# lampe.net
KiCad netlist of a schematic drawn in EAGLE
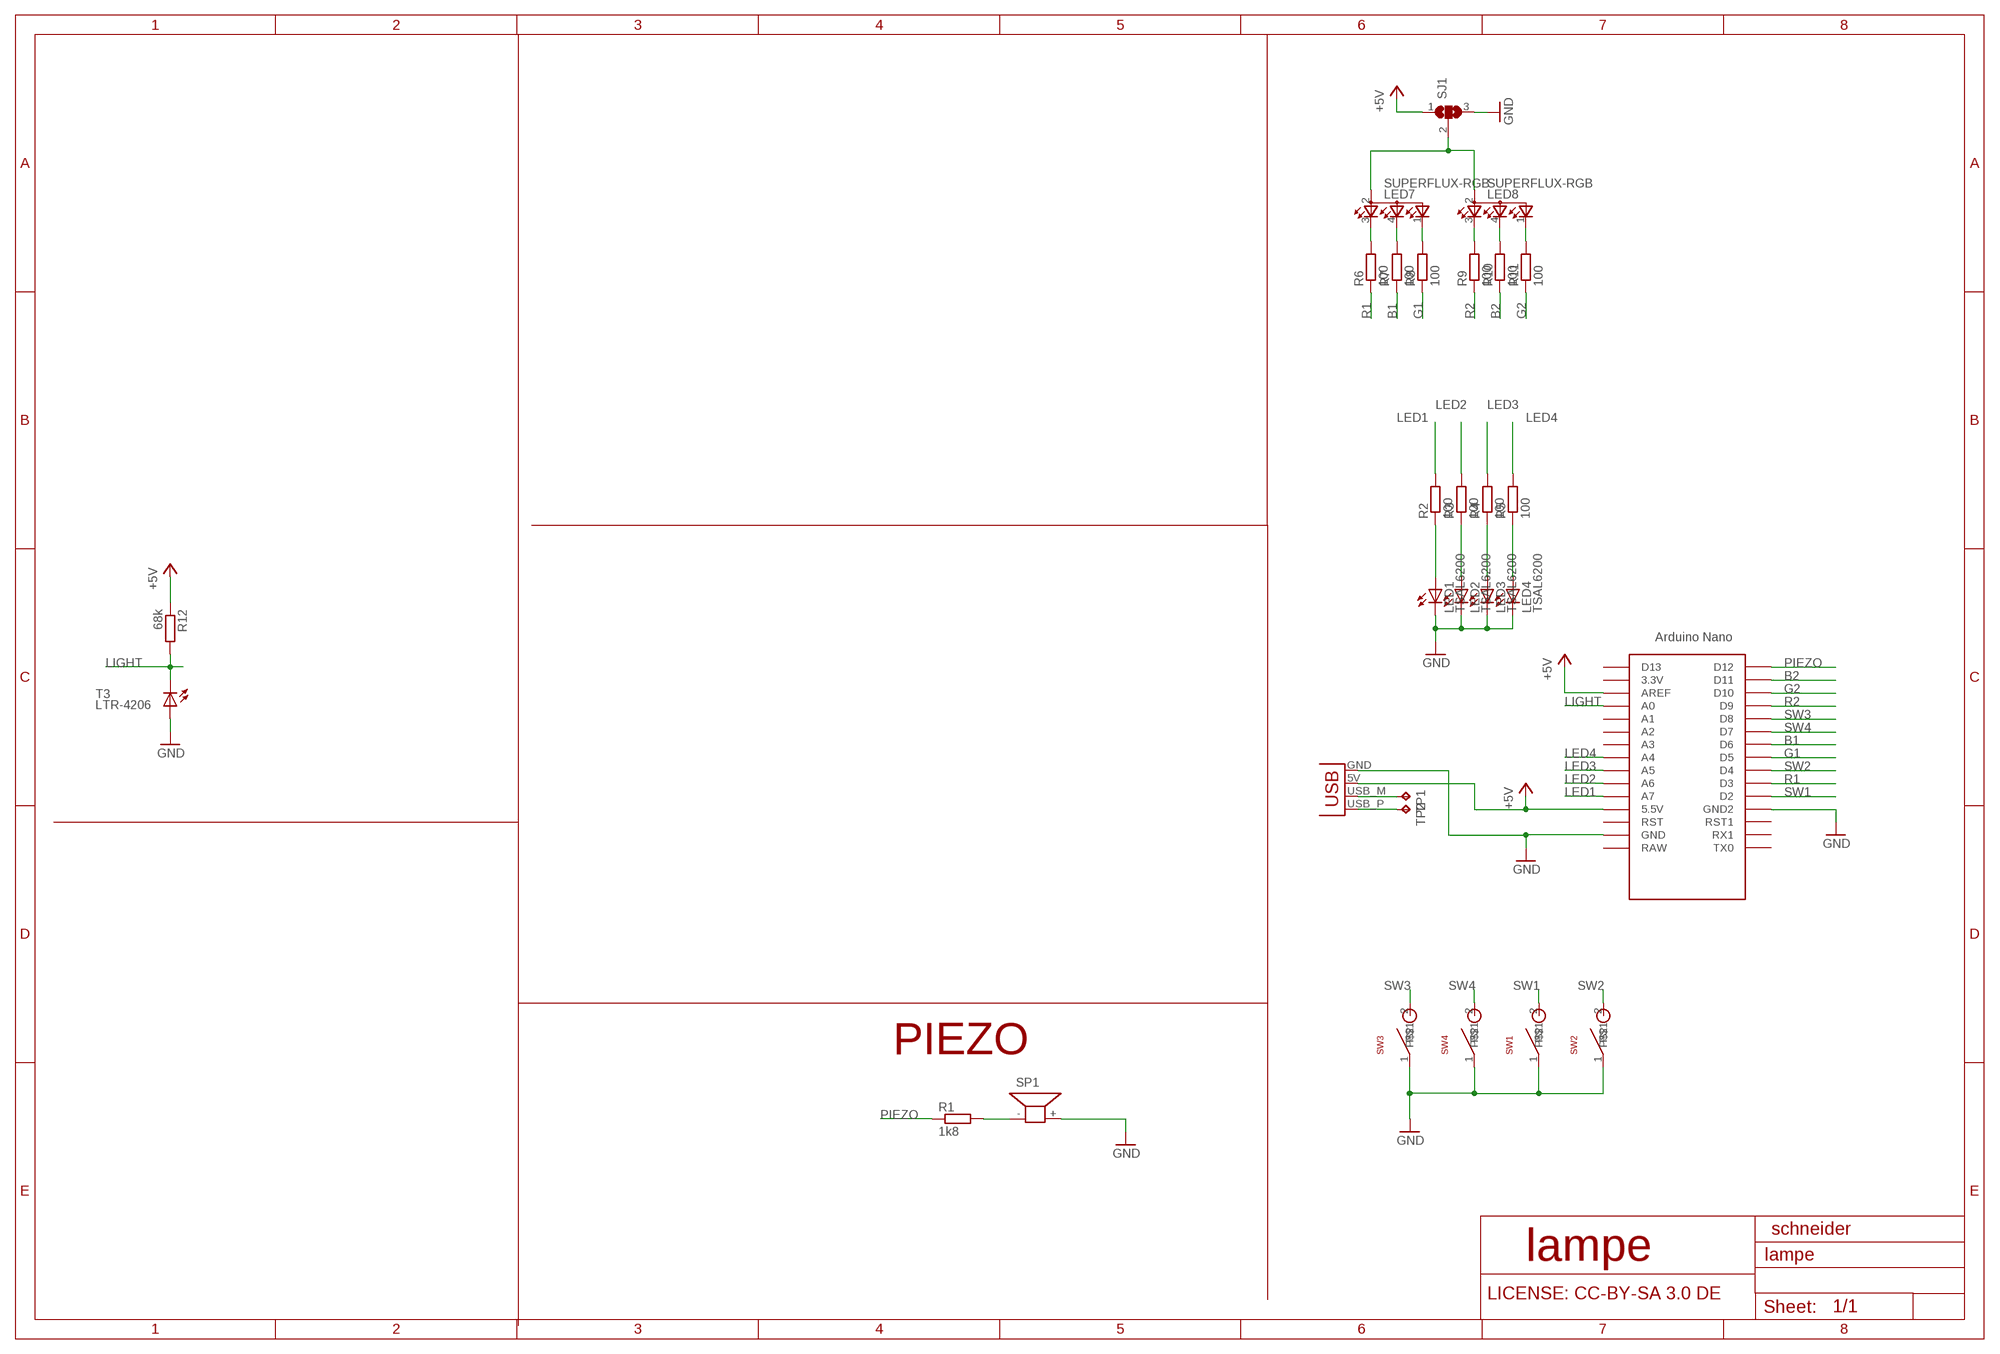
[diagram p0: schematic, sheet 1]

(export (version "E")
  (design (tool "Eeschema 10.0.6"))
  (components
    (comp (ref "LED1")
      (value "TSAL6200")
      (footprint "eagle-import:LED5MM")
      (libsource (lib "eagle-import") (part "LED5MM"))
    )
    (comp (ref "LED2")
      (value "TSAL6200")
      (footprint "eagle-import:LED5MM")
      (libsource (lib "eagle-import") (part "LED5MM"))
    )
    (comp (ref "LED3")
      (value "TSAL6200")
      (footprint "eagle-import:LED5MM")
      (libsource (lib "eagle-import") (part "LED5MM"))
    )
    (comp (ref "LED4")
      (value "TSAL6200")
      (footprint "eagle-import:LED5MM")
      (libsource (lib "eagle-import") (part "LED5MM"))
    )
    (comp (ref "LED7")
      (value "SUPERFLUX-RGB")
      (footprint "eagle-import:SUPERFLUX-7.6X7.6")
      (libsource (lib "eagle-import") (part "SUPERFLUX-RGB"))
    )
    (comp (ref "LED8")
      (value "SUPERFLUX-RGB")
      (footprint "eagle-import:SUPERFLUX-7.6X7.6")
      (libsource (lib "eagle-import") (part "SUPERFLUX-RGB"))
    )
    (comp (ref "R1")
      (value "1k8")
      (footprint "eagle-import:0207_7")
      (libsource (lib "eagle-import") (part "R-EU_0207/7"))
    )
    (comp (ref "R2")
      (value "100")
      (footprint "eagle-import:0207_7")
      (libsource (lib "eagle-import") (part "R-EU_0207/7"))
    )
    (comp (ref "R3")
      (value "100")
      (footprint "eagle-import:0207_7")
      (libsource (lib "eagle-import") (part "R-EU_0207/7"))
    )
    (comp (ref "R4")
      (value "100")
      (footprint "eagle-import:0207_7")
      (libsource (lib "eagle-import") (part "R-EU_0207/7"))
    )
    (comp (ref "R5")
      (value "100")
      (footprint "eagle-import:0207_7")
      (libsource (lib "eagle-import") (part "R-EU_0207/7"))
    )
    (comp (ref "R6")
      (value "100")
      (footprint "eagle-import:0207_7")
      (libsource (lib "eagle-import") (part "R-EU_0207/7"))
    )
    (comp (ref "R7")
      (value "100")
      (footprint "eagle-import:0207_7")
      (libsource (lib "eagle-import") (part "R-EU_0207/7"))
    )
    (comp (ref "R8")
      (value "100")
      (footprint "eagle-import:0207_7")
      (libsource (lib "eagle-import") (part "R-EU_0207/7"))
    )
    (comp (ref "R9")
      (value "100")
      (footprint "eagle-import:0207_7")
      (libsource (lib "eagle-import") (part "R-EU_0207/7"))
    )
    (comp (ref "R10")
      (value "100")
      (footprint "eagle-import:0207_7")
      (libsource (lib "eagle-import") (part "R-EU_0207/7"))
    )
    (comp (ref "R11")
      (value "100")
      (footprint "eagle-import:0207_7")
      (libsource (lib "eagle-import") (part "R-EU_0207/7"))
    )
    (comp (ref "R12")
      (value "68k")
      (footprint "eagle-import:0207_7")
      (libsource (lib "eagle-import") (part "R-EU_0207/7"))
    )
    (comp (ref "SJ1")
      (value "SJ2W")
      (footprint "eagle-import:SJ_2")
      (libsource (lib "eagle-import") (part "SJ2W"))
    )
    (comp (ref "SP1")
      (value "AL11P")
      (footprint "eagle-import:AL11P")
      (libsource (lib "eagle-import") (part "AL11P"))
    )
    (comp (ref "SW1")
      (value "SWITCH")
      (footprint "eagle-import:SWITCH")
      (libsource (lib "eagle-import") (part "SWITCH"))
    )
    (comp (ref "SW2")
      (value "SWITCH")
      (footprint "eagle-import:SWITCH")
      (libsource (lib "eagle-import") (part "SWITCH"))
    )
    (comp (ref "SW3")
      (value "SWITCH")
      (footprint "eagle-import:SWITCH")
      (libsource (lib "eagle-import") (part "SWITCH"))
    )
    (comp (ref "SW4")
      (value "SWITCH")
      (footprint "eagle-import:SWITCH")
      (libsource (lib "eagle-import") (part "SWITCH"))
    )
    (comp (ref "T3")
      (value "LTR-4206")
      (footprint "eagle-import:LED3MM")
      (libsource (lib "eagle-import") (part "LED3MM"))
    )
    (comp (ref "TP1")
      (value "TPB1,27")
      (footprint "eagle-import:B1,27")
      (libsource (lib "eagle-import") (part "TPB1,27"))
    )
    (comp (ref "TP2")
      (value "TPB1,27")
      (footprint "eagle-import:B1,27")
      (libsource (lib "eagle-import") (part "TPB1,27"))
    )
    (comp (ref "U$1")
      (value "NANO")
      (footprint "eagle-import:NANO")
      (libsource (lib "eagle-import") (part "NANO"))
    )
    (comp (ref "X1")
      (value "USBPCB")
      (footprint "eagle-import:USB-A-PCB")
      (libsource (lib "eagle-import") (part "USBPCB"))
    )
  )
  (nets
    (net (code "1") (name "+5V") (class "Default")
      (node (ref "R12") (pin "1") (pinfunction "1_1") (pintype "passive"))
      (node (ref "SJ1") (pin "1") (pinfunction "1_1") (pintype "passive"))
      (node (ref "U$1") (pin "5V") (pinfunction "5.5V_5V") (pintype "bidirectional"))
      (node (ref "U$1") (pin "AREF") (pinfunction "AREF_AREF") (pintype "bidirectional"))
      (node (ref "X1") (pin "5V") (pinfunction "VBUS_5V") (pintype "bidirectional"))
    )
    (net (code "2") (name "/B1") (class "Default")
      (node (ref "R7") (pin "1") (pinfunction "1_1") (pintype "passive"))
      (node (ref "U$1") (pin "D6") (pinfunction "D6_D6") (pintype "bidirectional"))
    )
    (net (code "3") (name "/B2") (class "Default")
      (node (ref "R10") (pin "1") (pinfunction "1_1") (pintype "passive"))
      (node (ref "U$1") (pin "D11") (pinfunction "D11_D11") (pintype "bidirectional"))
    )
    (net (code "4") (name "/G1") (class "Default")
      (node (ref "R8") (pin "1") (pinfunction "1_1") (pintype "passive"))
      (node (ref "U$1") (pin "D5") (pinfunction "D5_D5") (pintype "bidirectional"))
    )
    (net (code "5") (name "/G2") (class "Default")
      (node (ref "R11") (pin "1") (pinfunction "1_1") (pintype "passive"))
      (node (ref "U$1") (pin "D10") (pinfunction "D10_D10") (pintype "bidirectional"))
    )
    (net (code "6") (name "/LED1") (class "Default")
      (node (ref "R2") (pin "2") (pinfunction "2_2") (pintype "passive"))
      (node (ref "U$1") (pin "A7") (pinfunction "A7_A7") (pintype "bidirectional"))
    )
    (net (code "7") (name "/LED2") (class "Default")
      (node (ref "R3") (pin "2") (pinfunction "2_2") (pintype "passive"))
      (node (ref "U$1") (pin "A6") (pinfunction "A6_A6") (pintype "bidirectional"))
    )
    (net (code "8") (name "/LED3") (class "Default")
      (node (ref "R4") (pin "2") (pinfunction "2_2") (pintype "passive"))
      (node (ref "U$1") (pin "A5") (pinfunction "A5_A5") (pintype "bidirectional"))
    )
    (net (code "9") (name "/LED4") (class "Default")
      (node (ref "R5") (pin "2") (pinfunction "2_2") (pintype "passive"))
      (node (ref "U$1") (pin "A4") (pinfunction "A4_A4") (pintype "bidirectional"))
    )
    (net (code "10") (name "/LIGHT") (class "Default")
      (node (ref "R12") (pin "2") (pinfunction "2_2") (pintype "passive"))
      (node (ref "T3") (pin "K") (pinfunction "C_K") (pintype "passive"))
      (node (ref "U$1") (pin "A0") (pinfunction "A0_A0") (pintype "bidirectional"))
    )
    (net (code "11") (name "/PIEZO") (class "Default")
      (node (ref "R1") (pin "1") (pinfunction "1_1") (pintype "passive"))
      (node (ref "U$1") (pin "D12") (pinfunction "D12_D12") (pintype "bidirectional"))
    )
    (net (code "12") (name "/R1") (class "Default")
      (node (ref "R6") (pin "1") (pinfunction "1_1") (pintype "passive"))
      (node (ref "U$1") (pin "D3") (pinfunction "D3_D3") (pintype "bidirectional"))
    )
    (net (code "13") (name "/R2") (class "Default")
      (node (ref "R9") (pin "1") (pinfunction "1_1") (pintype "passive"))
      (node (ref "U$1") (pin "D9") (pinfunction "D9_D9") (pintype "bidirectional"))
    )
    (net (code "14") (name "/SW1") (class "Default")
      (node (ref "SW1") (pin "2") (pinfunction "P$2_2") (pintype "bidirectional"))
      (node (ref "U$1") (pin "D2") (pinfunction "D2_D2") (pintype "bidirectional"))
    )
    (net (code "15") (name "/SW2") (class "Default")
      (node (ref "SW2") (pin "2") (pinfunction "P$2_2") (pintype "bidirectional"))
      (node (ref "U$1") (pin "D4") (pinfunction "D4_D4") (pintype "bidirectional"))
    )
    (net (code "16") (name "/SW3") (class "Default")
      (node (ref "SW3") (pin "2") (pinfunction "P$2_2") (pintype "bidirectional"))
      (node (ref "U$1") (pin "D8") (pinfunction "D8_D8") (pintype "bidirectional"))
    )
    (net (code "17") (name "/SW4") (class "Default")
      (node (ref "SW4") (pin "2") (pinfunction "P$2_2") (pintype "bidirectional"))
      (node (ref "U$1") (pin "D7") (pinfunction "D7_D7") (pintype "bidirectional"))
    )
    (net (code "18") (name "GND") (class "Default")
      (node (ref "LED1") (pin "K") (pinfunction "C_K") (pintype "passive"))
      (node (ref "LED2") (pin "K") (pinfunction "C_K") (pintype "passive"))
      (node (ref "LED3") (pin "K") (pinfunction "C_K") (pintype "passive"))
      (node (ref "LED4") (pin "K") (pinfunction "C_K") (pintype "passive"))
      (node (ref "SJ1") (pin "3") (pinfunction "3_3") (pintype "passive"))
      (node (ref "SP1") (pin "+") (pinfunction "2_+") (pintype "passive"))
      (node (ref "SW1") (pin "1") (pinfunction "P$1_1") (pintype "bidirectional"))
      (node (ref "SW2") (pin "1") (pinfunction "P$1_1") (pintype "bidirectional"))
      (node (ref "SW3") (pin "1") (pinfunction "P$1_1") (pintype "bidirectional"))
      (node (ref "SW4") (pin "1") (pinfunction "P$1_1") (pintype "bidirectional"))
      (node (ref "T3") (pin "A") (pinfunction "A_A") (pintype "passive"))
      (node (ref "U$1") (pin "GND") (pinfunction "GND_GND") (pintype "bidirectional"))
      (node (ref "U$1") (pin "GND1") (pinfunction "GND2_GND1") (pintype "bidirectional"))
      (node (ref "X1") (pin "GND") (pinfunction "GND_GND") (pintype "bidirectional"))
    )
    (net (code "19") (name "Net-(LED1-PadA)") (class "Default")
      (node (ref "LED1") (pin "A") (pinfunction "A_A") (pintype "passive"))
      (node (ref "R2") (pin "1") (pinfunction "1_1") (pintype "passive"))
    )
    (net (code "20") (name "Net-(LED2-PadA)") (class "Default")
      (node (ref "LED2") (pin "A") (pinfunction "A_A") (pintype "passive"))
      (node (ref "R3") (pin "1") (pinfunction "1_1") (pintype "passive"))
    )
    (net (code "21") (name "Net-(LED3-PadA)") (class "Default")
      (node (ref "LED3") (pin "A") (pinfunction "A_A") (pintype "passive"))
      (node (ref "R4") (pin "1") (pinfunction "1_1") (pintype "passive"))
    )
    (net (code "22") (name "Net-(LED4-PadA)") (class "Default")
      (node (ref "LED4") (pin "A") (pinfunction "A_A") (pintype "passive"))
      (node (ref "R5") (pin "1") (pinfunction "1_1") (pintype "passive"))
    )
    (net (code "23") (name "Net-(LED7-A2)") (class "Default")
      (node (ref "LED7") (pin "2") (pinfunction "A2_2") (pintype "passive"))
      (node (ref "LED8") (pin "2") (pinfunction "A2_2") (pintype "passive"))
      (node (ref "SJ1") (pin "2") (pinfunction "2_2") (pintype "passive"))
    )
    (net (code "24") (name "Net-(LED7-CBLUE)") (class "Default")
      (node (ref "LED7") (pin "4") (pinfunction "CBLUE_4") (pintype "passive"))
      (node (ref "R7") (pin "2") (pinfunction "2_2") (pintype "passive"))
    )
    (net (code "25") (name "Net-(LED7-CGREEN)") (class "Default")
      (node (ref "LED7") (pin "1") (pinfunction "CGREEN_1") (pintype "passive"))
      (node (ref "R8") (pin "2") (pinfunction "2_2") (pintype "passive"))
    )
    (net (code "26") (name "Net-(LED7-CRED)") (class "Default")
      (node (ref "LED7") (pin "3") (pinfunction "CRED_3") (pintype "passive"))
      (node (ref "R6") (pin "2") (pinfunction "2_2") (pintype "passive"))
    )
    (net (code "27") (name "Net-(LED8-CBLUE)") (class "Default")
      (node (ref "LED8") (pin "4") (pinfunction "CBLUE_4") (pintype "passive"))
      (node (ref "R10") (pin "2") (pinfunction "2_2") (pintype "passive"))
    )
    (net (code "28") (name "Net-(LED8-CGREEN)") (class "Default")
      (node (ref "LED8") (pin "1") (pinfunction "CGREEN_1") (pintype "passive"))
      (node (ref "R11") (pin "2") (pinfunction "2_2") (pintype "passive"))
    )
    (net (code "29") (name "Net-(LED8-CRED)") (class "Default")
      (node (ref "LED8") (pin "3") (pinfunction "CRED_3") (pintype "passive"))
      (node (ref "R9") (pin "2") (pinfunction "2_2") (pintype "passive"))
    )
    (net (code "30") (name "Net-(SP1-1)") (class "Default")
      (node (ref "R1") (pin "2") (pinfunction "2_2") (pintype "passive"))
      (node (ref "SP1") (pin "-") (pinfunction "1_-") (pintype "passive"))
    )
    (net (code "31") (name "Net-(X1-D+)") (class "Default")
      (node (ref "TP2") (pin "TP") (pinfunction "TP_TP") (pintype "input"))
      (node (ref "X1") (pin "USB_P") (pinfunction "D+_USB_P") (pintype "bidirectional"))
    )
    (net (code "32") (name "Net-(X1-D-)") (class "Default")
      (node (ref "TP1") (pin "TP") (pinfunction "TP_TP") (pintype "input"))
      (node (ref "X1") (pin "USB_M") (pinfunction "D-_USB_M") (pintype "bidirectional"))
    )
    (net (code "33") (name "unconnected-(U$1-Pad3.3V)") (class "Default")
      (node (ref "U$1") (pin "3.3V") (pinfunction "3.3V_3.3V") (pintype "bidirectional"))
    )
    (net (code "34") (name "unconnected-(U$1-PadA1)") (class "Default")
      (node (ref "U$1") (pin "A1") (pinfunction "A1_A1") (pintype "bidirectional"))
    )
    (net (code "35") (name "unconnected-(U$1-PadA2)") (class "Default")
      (node (ref "U$1") (pin "A2") (pinfunction "A2_A2") (pintype "bidirectional"))
    )
    (net (code "36") (name "unconnected-(U$1-PadA3)") (class "Default")
      (node (ref "U$1") (pin "A3") (pinfunction "A3_A3") (pintype "bidirectional"))
    )
    (net (code "37") (name "unconnected-(U$1-PadD13)") (class "Default")
      (node (ref "U$1") (pin "D13") (pinfunction "D13_D13") (pintype "bidirectional"))
    )
    (net (code "38") (name "unconnected-(U$1-PadRAW)") (class "Default")
      (node (ref "U$1") (pin "RAW") (pinfunction "RAW_RAW") (pintype "bidirectional"))
    )
    (net (code "39") (name "unconnected-(U$1-PadRST)") (class "Default")
      (node (ref "U$1") (pin "RST") (pinfunction "RST_RST") (pintype "bidirectional"))
    )
    (net (code "40") (name "unconnected-(U$1-PadRST1)") (class "Default")
      (node (ref "U$1") (pin "RST1") (pinfunction "RST1_RST1") (pintype "bidirectional"))
    )
    (net (code "41") (name "unconnected-(U$1-PadRX1)") (class "Default")
      (node (ref "U$1") (pin "RX1") (pinfunction "RX1_RX1") (pintype "bidirectional"))
    )
    (net (code "42") (name "unconnected-(U$1-PadTX0)") (class "Default")
      (node (ref "U$1") (pin "TX0") (pinfunction "TX0_TX0") (pintype "bidirectional"))
    )
  )
)
